# Thermistor_Channel.net
KiCad netlist of a schematic drawn in Altium Designer
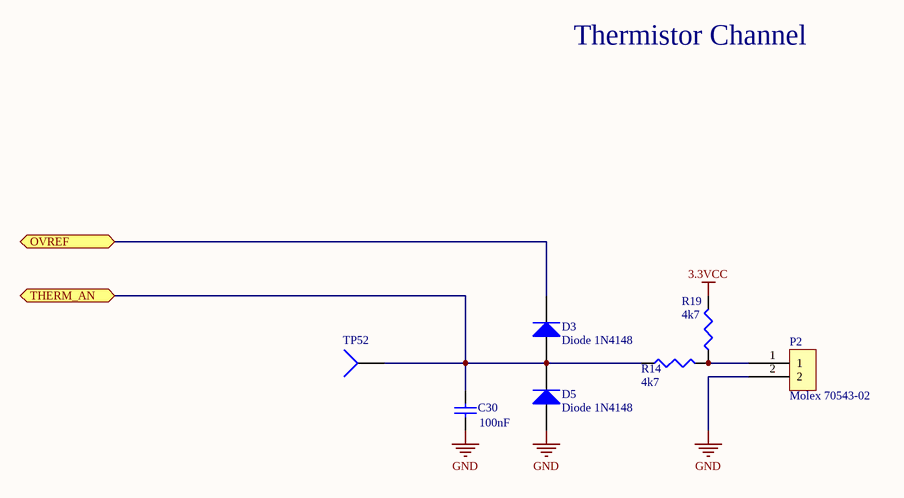
[diagram p0: Thermistor Channel.SchDoc]

(export (version "E")
  (design (tool "Eeschema 10.0.6"))
  (components
    (comp (ref "C30")
      (value "100nF")
      (footprint "1608[0603]")
      (description "Capacitor (Semiconductor SIM Model)")
      (fields (field (name "Comment") "Cap Semi") (field (name "PUBLISHER") "Altium Limited"))
      (libsource (lib "Miscellaneous Devices") (part "Cap Semi"))
    )
    (comp (ref "D3")
      (value "Diode 1N4148")
      (footprint "1N4148WT")
      (description "High Conductance Fast Diode")
      (fields (field (name "PUBLISHER") "Altium Limited"))
      (libsource (lib "Miscellaneous Devices") (part "Diode 1N4148"))
    )
    (comp (ref "D5")
      (value "Diode 1N4148")
      (footprint "1N4148WT")
      (description "High Conductance Fast Diode")
      (fields (field (name "PUBLISHER") "Altium Limited"))
      (libsource (lib "Miscellaneous Devices") (part "Diode 1N4148"))
    )
    (comp (ref "P2")
      (value "Molex 70543-02")
      (footprint "70543-02")
      (libsource (lib "ZMBo Schematic Library") (part "Molex 70543-02"))
    )
    (comp (ref "R14")
      (value "4k7")
      (footprint "J1-0603")
      (description "Resistor")
      (fields (field (name "Comment") "Res3") (field (name "PUBLISHER") "Altium Limited"))
      (libsource (lib "Miscellaneous Devices") (part "Res3"))
    )
    (comp (ref "R19")
      (value "4k7")
      (footprint "J1-0603")
      (description "Resistor")
      (fields (field (name "Comment") "Res3") (field (name "PUBLISHER") "Altium Limited"))
      (libsource (lib "Miscellaneous Devices") (part "Res3"))
    )
    (comp (ref "TP52")
      (value "TP4")
      (footprint "TP-2")
      (description "Socket")
      (fields (field (name "PUBLISHER") "Altium Limited"))
      (libsource (lib "ZMBo Schematic Library") (part "Socket"))
    )
  )
  (nets
    (net (code "1") (name "/OVREF") (class "Default")
      (node (ref "D3") (pin "2") (pinfunction "K_2") (pintype "passive"))
    )
    (net (code "2") (name "/THERM_AN") (class "Default")
      (node (ref "C30") (pin "2") (pinfunction "2_2") (pintype "passive"))
      (node (ref "D3") (pin "1") (pinfunction "A_1") (pintype "passive"))
      (node (ref "D5") (pin "2") (pinfunction "K_2") (pintype "passive"))
      (node (ref "R14") (pin "1") (pinfunction "1_1") (pintype "passive"))
      (node (ref "TP52") (pin "1") (pinfunction "1_1") (pintype "passive"))
    )
    (net (code "3") (name "3.3VCC") (class "Default")
      (node (ref "R19") (pin "2") (pinfunction "2_2") (pintype "passive"))
    )
    (net (code "4") (name "GND") (class "Default")
      (node (ref "C30") (pin "1") (pinfunction "1_1") (pintype "passive"))
      (node (ref "D5") (pin "1") (pinfunction "A_1") (pintype "passive"))
      (node (ref "P2") (pin "2") (pinfunction "2_2") (pintype "passive"))
    )
    (net (code "5") (name "Net-(P2-Pad1)") (class "Default")
      (node (ref "P2") (pin "1") (pinfunction "1_1") (pintype "passive"))
      (node (ref "R14") (pin "2") (pinfunction "2_2") (pintype "passive"))
      (node (ref "R19") (pin "1") (pinfunction "1_1") (pintype "passive"))
    )
  )
)
